# Motor_Driver.net
KiCad netlist of a schematic drawn in Altium Designer
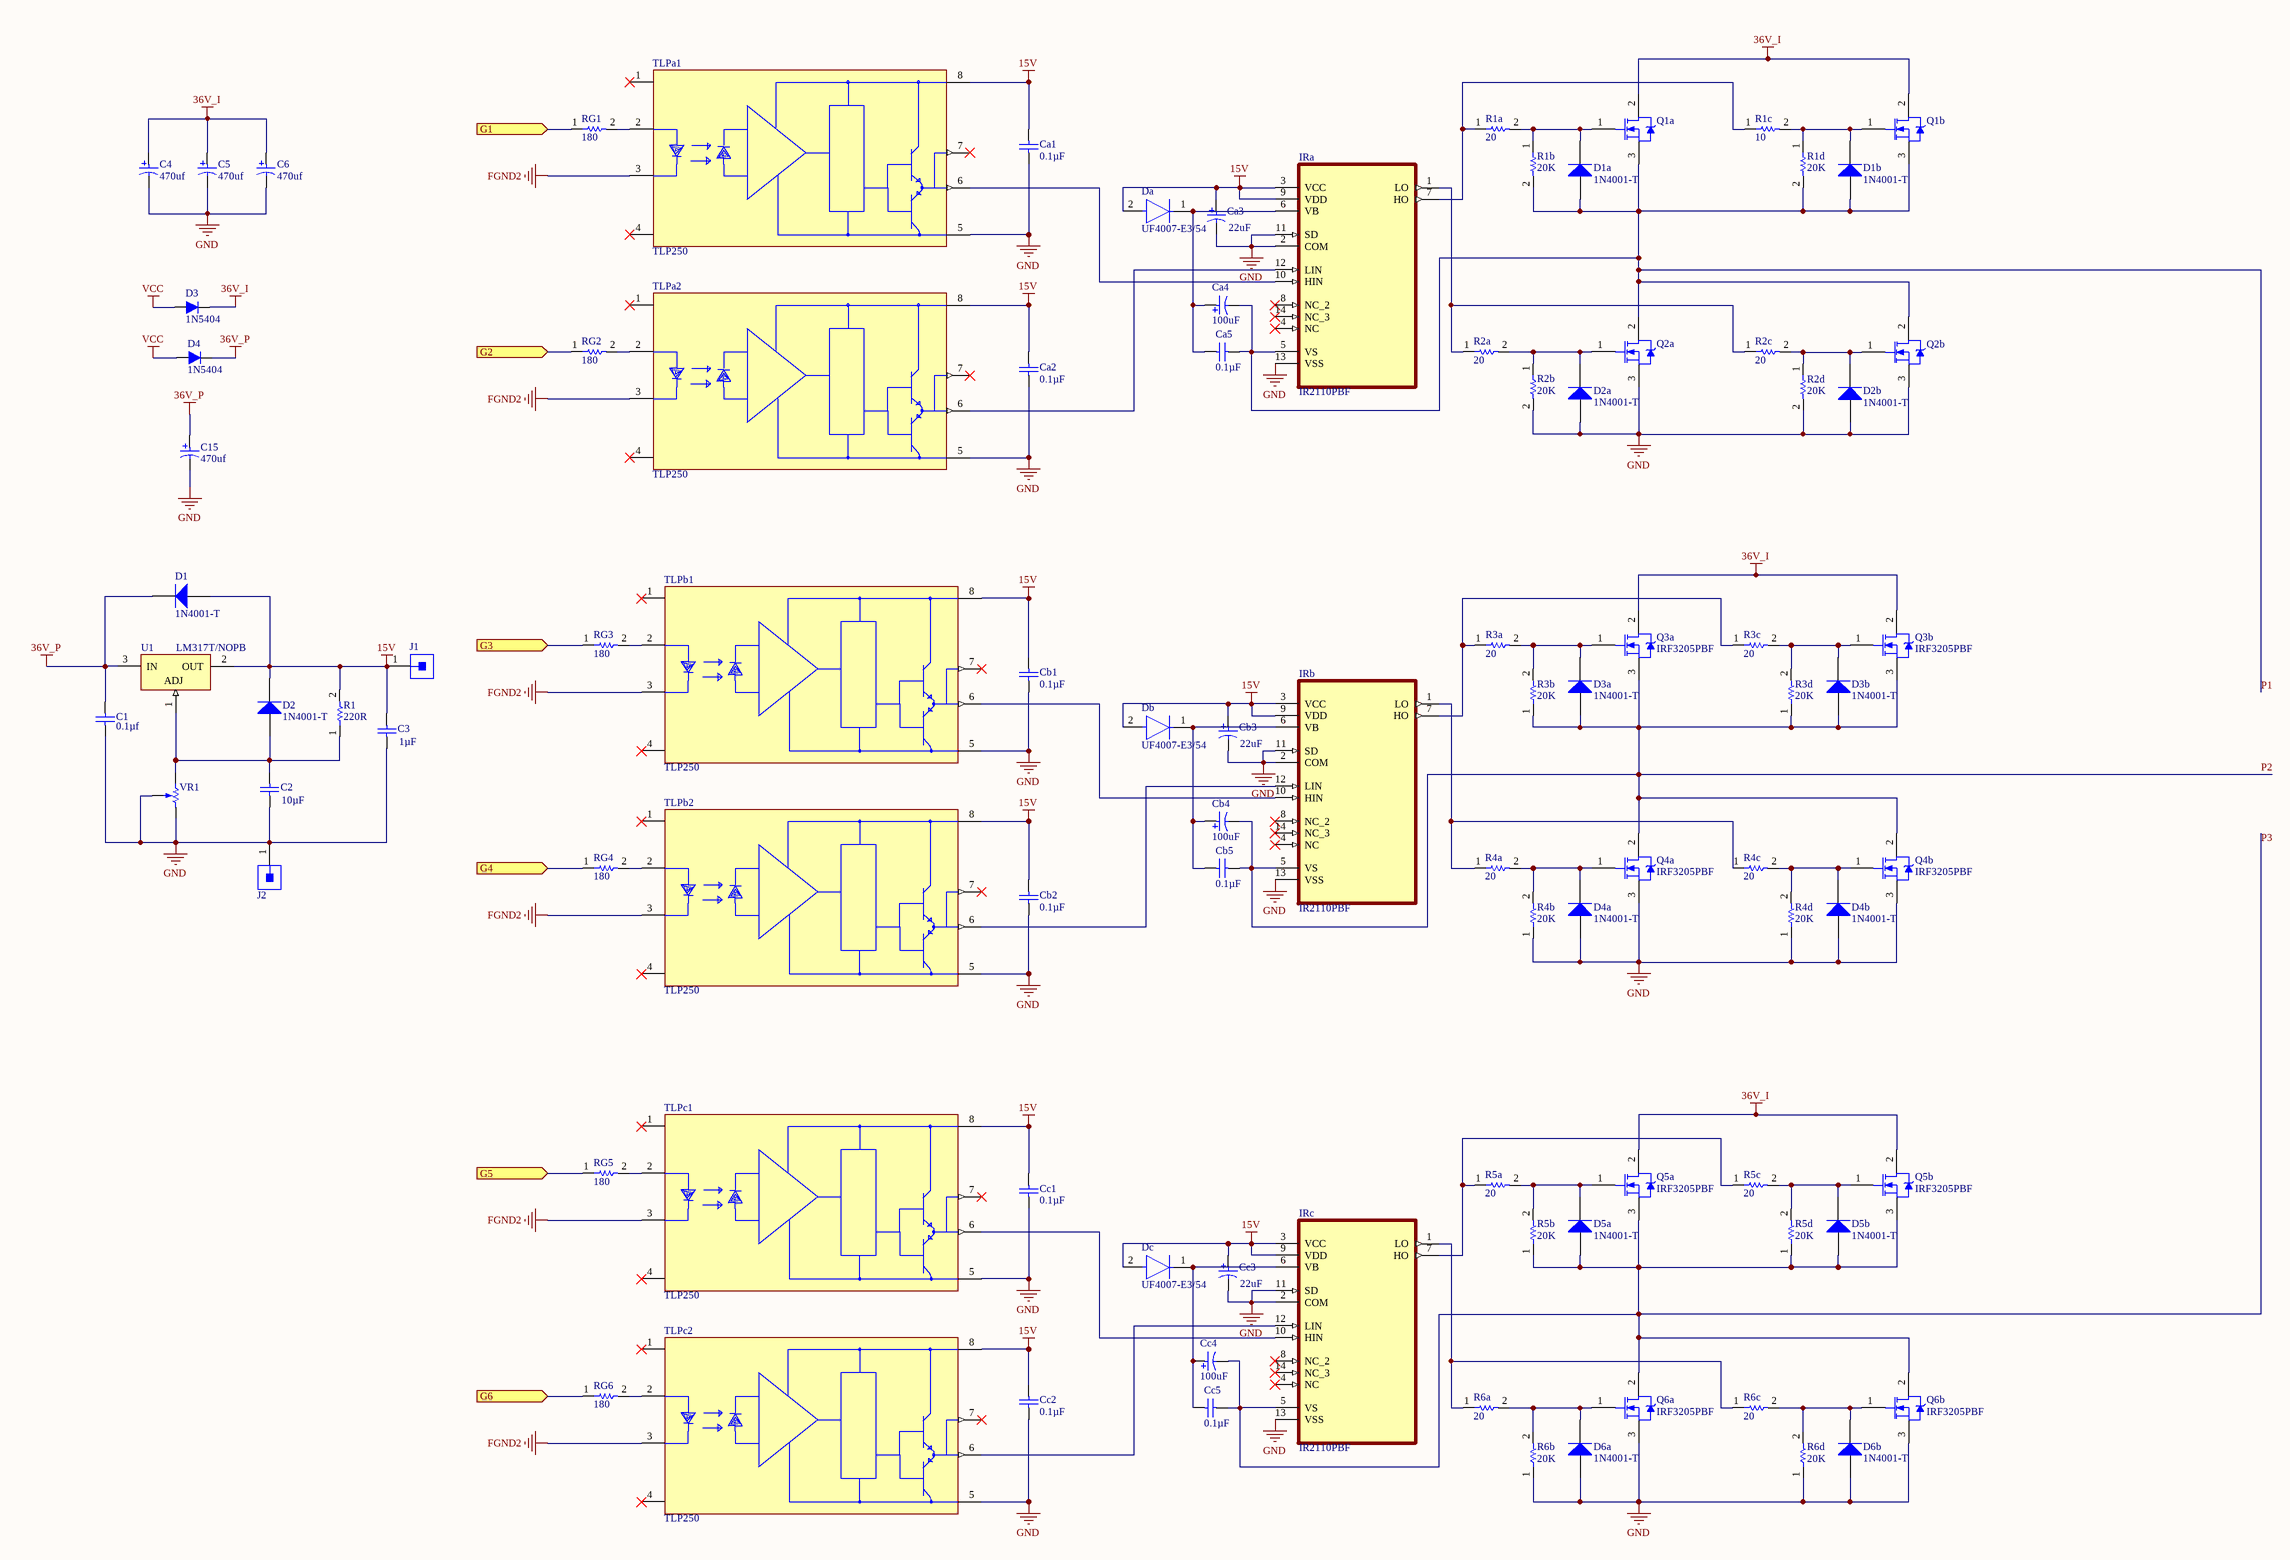
[diagram p0: Motor_Driver.SchDoc]

(export (version "E")
  (design (tool "Eeschema 10.0.6"))
  (components
    (comp (ref "C1")
      (value "0.1µf")
      (footprint "Cap-0.1uf-50V-Ceramic1")
      (description "Lead Capacitor X7R_EIA_ with Capacitance: 0.10F and Rated Voltage: 50Vdc")
      (fields (field (name "MP") "RDER71H104K0K1H03B") (field (name "MF") "Murata"))
      (libsource (lib "YAYAT-LIB") (part "Cap-0.1uf-50V-Ceramic_1"))
    )
    (comp (ref "C2")
      (value "K104K15X7RF5TL2")
      (footprint "Cap-0.1uf-50v-ceramic")
      (description "Ceramic Capacitor, 100 nF, +/- 10%, 50 V, -55 to 125 degC, 2-Pin THD, RoHS, Tape and Reel")
      (fields
        (field (name "MANUFACTURER") "Vishay")
        (field (name "TOLERANCE") "±10%")
        (field (name "CAPACITANCE") "10µF")
      )
      (libsource (lib "YAYAT-LIB") (part "Cap-0.1uf-50v-ceramic"))
    )
    (comp (ref "C3")
      (value "K104K15X7RF5TL2")
      (footprint "Cap-0.1uf-50v-ceramic")
      (description "Ceramic Capacitor, 100 nF, +/- 10%, 50 V, -55 to 125 degC, 2-Pin THD, RoHS, Tape and Reel")
      (fields
        (field (name "MANUFACTURER") "Vishay")
        (field (name "TOLERANCE") "±10%")
        (field (name "CAPACITANCE") "1µF")
      )
      (libsource (lib "YAYAT-LIB") (part "Cap-0.1uf-50v-ceramic"))
    )
    (comp (ref "C4")
      (value "470uf")
      (footprint "Cap-470uf-63v-radial")
      (description "Aluminum Electrolytic Capacitor, 470 uF, +/- 20%, 50 V, -40 to 85 degC, 2-Pin THD, RoHS, Bulk")
      (fields (field (name "TOLERANCE") "10%"))
      (libsource (lib "YAYAT-LIB") (part "Cap-470uf-63v-radial"))
    )
    (comp (ref "C5")
      (value "470uf")
      (footprint "Cap-470uf-63v-radial")
      (description "Aluminum Electrolytic Capacitor, 470 uF, +/- 20%, 50 V, -40 to 85 degC, 2-Pin THD, RoHS, Bulk")
      (fields (field (name "TOLERANCE") "10%"))
      (libsource (lib "YAYAT-LIB") (part "Cap-470uf-63v-radial"))
    )
    (comp (ref "C6")
      (value "470uf")
      (footprint "Cap-470uf-63v-radial")
      (description "Aluminum Electrolytic Capacitor, 470 uF, +/- 20%, 50 V, -40 to 85 degC, 2-Pin THD, RoHS, Bulk")
      (fields (field (name "TOLERANCE") "10%"))
      (libsource (lib "YAYAT-LIB") (part "Cap-470uf-63v-radial"))
    )
    (comp (ref "C15")
      (value "470uf")
      (footprint "Cap-470uf-63v-radial")
      (description "Aluminum Electrolytic Capacitor, 470 uF, +/- 20%, 50 V, -40 to 85 degC, 2-Pin THD, RoHS, Bulk")
      (fields (field (name "TOLERANCE") "10%"))
      (libsource (lib "YAYAT-LIB") (part "Cap-470uf-63v-radial"))
    )
    (comp (ref "Ca1")
      (value "0.1µF")
      (footprint "Cap-0.1uf-50V-Ceramic1")
      (description "Lead Capacitor X7R_EIA_ with Capacitance: 0.10F and Rated Voltage: 50Vdc")
      (fields (field (name "MP") "RDER71H104K0K1H03B") (field (name "MF") "Murata"))
      (libsource (lib "YAYAT-LIB") (part "Cap-0.1uf-50V-Ceramic_1"))
    )
    (comp (ref "Ca2")
      (value "0.1µF")
      (footprint "Cap-0.1uf-50V-Ceramic1")
      (description "Lead Capacitor X7R_EIA_ with Capacitance: 0.10F and Rated Voltage: 50Vdc")
      (fields (field (name "MP") "RDER71H104K0K1H03B") (field (name "MF") "Murata"))
      (libsource (lib "YAYAT-LIB") (part "Cap-0.1uf-50V-Ceramic_1"))
    )
    (comp (ref "Ca3")
      (value "ECA1HM220")
      (footprint "CAP-22uf-50v-radial")
      (description "Aluminum Electrolytic Capacitor, 22 uF, +/- 20%, 50 V, -40 to 85 degC, 2-Pin THD, RoHS, Bulk")
      (fields
        (field (name "VOLTAGE") "50V")
        (field (name "MANUFACTURER") "Panasonic")
        (field (name "CAPACITANCE") "22uF")
      )
      (libsource (lib "YAYAT-LIB") (part "Cap-22uf-50v-radial"))
    )
    (comp (ref "Ca4")
      (value "ECA1HM101")
      (footprint "Cap-100uf-50v-radial")
      (description "Aluminum Electrolytic Capacitor, 100 uF, +/- 20%, 50 V, -40 to 85 degC, 2-Pin THD, RoHS, Bulk")
      (fields
        (field (name "MANUFACTURER") "Panasonic")
        (field (name "VOLTAGE") "50V")
        (field (name "CAPACITANCE") "100uF")
      )
      (libsource (lib "YAYAT-LIB") (part "Cap-100uf-50v-radial"))
    )
    (comp (ref "Ca5")
      (value "0.1µF")
      (footprint "Cap-0.1uf-50V-Ceramic1")
      (description "Lead Capacitor X7R_EIA_ with Capacitance: 0.10F and Rated Voltage: 50Vdc")
      (fields (field (name "MP") "RDER71H104K0K1H03B") (field (name "MF") "Murata"))
      (libsource (lib "YAYAT-LIB") (part "Cap-0.1uf-50V-Ceramic_1"))
    )
    (comp (ref "Cb1")
      (value "0.1µF")
      (footprint "Cap-0.1uf-50V-Ceramic1")
      (description "Lead Capacitor X7R_EIA_ with Capacitance: 0.10F and Rated Voltage: 50Vdc")
      (fields (field (name "MP") "RDER71H104K0K1H03B") (field (name "MF") "Murata"))
      (libsource (lib "YAYAT-LIB") (part "Cap-0.1uf-50V-Ceramic_1"))
    )
    (comp (ref "Cb2")
      (value "0.1µF")
      (footprint "Cap-0.1uf-50V-Ceramic1")
      (description "Lead Capacitor X7R_EIA_ with Capacitance: 0.10F and Rated Voltage: 50Vdc")
      (fields (field (name "MP") "RDER71H104K0K1H03B") (field (name "MF") "Murata"))
      (libsource (lib "YAYAT-LIB") (part "Cap-0.1uf-50V-Ceramic_1"))
    )
    (comp (ref "Cb3")
      (value "ECA1HM220")
      (footprint "CAP-22uf-50v-radial")
      (description "Aluminum Electrolytic Capacitor, 22 uF, +/- 20%, 50 V, -40 to 85 degC, 2-Pin THD, RoHS, Bulk")
      (fields
        (field (name "VOLTAGE") "50V")
        (field (name "MANUFACTURER") "Panasonic")
        (field (name "CAPACITANCE") "22uF")
      )
      (libsource (lib "YAYAT-LIB") (part "Cap-22uf-50v-radial"))
    )
    (comp (ref "Cb4")
      (value "ECA1HM101")
      (footprint "Cap-100uf-50v-radial")
      (description "Aluminum Electrolytic Capacitor, 100 uF, +/- 20%, 50 V, -40 to 85 degC, 2-Pin THD, RoHS, Bulk")
      (fields
        (field (name "MANUFACTURER") "Panasonic")
        (field (name "VOLTAGE") "50V")
        (field (name "CAPACITANCE") "100uF")
      )
      (libsource (lib "YAYAT-LIB") (part "Cap-100uf-50v-radial"))
    )
    (comp (ref "Cb5")
      (value "0.1µF")
      (footprint "Cap-0.1uf-50V-Ceramic1")
      (description "Lead Capacitor X7R_EIA_ with Capacitance: 0.10F and Rated Voltage: 50Vdc")
      (fields (field (name "MP") "RDER71H104K0K1H03B") (field (name "MF") "Murata"))
      (libsource (lib "YAYAT-LIB") (part "Cap-0.1uf-50V-Ceramic_1"))
    )
    (comp (ref "Cc1")
      (value "0.1µF")
      (footprint "Cap-0.1uf-50V-Ceramic1")
      (description "Lead Capacitor X7R_EIA_ with Capacitance: 0.10F and Rated Voltage: 50Vdc")
      (fields (field (name "MP") "RDER71H104K0K1H03B") (field (name "MF") "Murata"))
      (libsource (lib "YAYAT-LIB") (part "Cap-0.1uf-50V-Ceramic_1"))
    )
    (comp (ref "Cc2")
      (value "0.1µF")
      (footprint "Cap-0.1uf-50V-Ceramic1")
      (description "Lead Capacitor X7R_EIA_ with Capacitance: 0.10F and Rated Voltage: 50Vdc")
      (fields (field (name "MP") "RDER71H104K0K1H03B") (field (name "MF") "Murata"))
      (libsource (lib "YAYAT-LIB") (part "Cap-0.1uf-50V-Ceramic_1"))
    )
    (comp (ref "Cc3")
      (value "ECA1HM220")
      (footprint "CAP-22uf-50v-radial")
      (description "Aluminum Electrolytic Capacitor, 22 uF, +/- 20%, 50 V, -40 to 85 degC, 2-Pin THD, RoHS, Bulk")
      (fields
        (field (name "VOLTAGE") "50V")
        (field (name "MANUFACTURER") "Panasonic")
        (field (name "CAPACITANCE") "22uF")
      )
      (libsource (lib "YAYAT-LIB") (part "Cap-22uf-50v-radial"))
    )
    (comp (ref "Cc4")
      (value "ECA1HM101")
      (footprint "Cap-100uf-50v-radial")
      (description "Aluminum Electrolytic Capacitor, 100 uF, +/- 20%, 50 V, -40 to 85 degC, 2-Pin THD, RoHS, Bulk")
      (fields
        (field (name "MANUFACTURER") "Panasonic")
        (field (name "VOLTAGE") "50V")
        (field (name "CAPACITANCE") "100uF")
      )
      (libsource (lib "YAYAT-LIB") (part "Cap-100uf-50v-radial"))
    )
    (comp (ref "Cc5")
      (value "0.1µF")
      (footprint "Cap-0.1uf-50V-Ceramic1")
      (description "Lead Capacitor X7R_EIA_ with Capacitance: 0.10F and Rated Voltage: 50Vdc")
      (fields (field (name "MP") "RDER71H104K0K1H03B") (field (name "MF") "Murata"))
      (libsource (lib "YAYAT-LIB") (part "Cap-0.1uf-50V-Ceramic_1"))
    )
    (comp (ref "D1")
      (value "1N4001-T")
      (footprint "Diode-1N4001")
      (description "1.0 A Rectifier, 15 pF, 50 V, -65 to 150 degC, 2-Pin DO-41 Plastic, RoHS, Tape and Reel")
      (fields (field (name "MANUFACTURER") "Diodes Inc"))
      (libsource (lib "YAYAT-LIB") (part "Diode-1N4001"))
    )
    (comp (ref "D1a")
      (value "1N4001-T")
      (footprint "Diode-1N4001")
      (description "1.0 A Rectifier, 15 pF, 50 V, -65 to 150 degC, 2-Pin DO-41 Plastic, RoHS, Tape and Reel")
      (fields (field (name "MANUFACTURER") "Diodes Inc"))
      (libsource (lib "YAYAT-LIB") (part "Diode-1N4001"))
    )
    (comp (ref "D1b")
      (value "1N4001-T")
      (footprint "Diode-1N4001")
      (description "1.0 A Rectifier, 15 pF, 50 V, -65 to 150 degC, 2-Pin DO-41 Plastic, RoHS, Tape and Reel")
      (fields (field (name "MANUFACTURER") "Diodes Inc"))
      (libsource (lib "YAYAT-LIB") (part "Diode-1N4001"))
    )
    (comp (ref "D2")
      (value "1N4001-T")
      (footprint "Diode-1N4001")
      (description "1.0 A Rectifier, 15 pF, 50 V, -65 to 150 degC, 2-Pin DO-41 Plastic, RoHS, Tape and Reel")
      (fields (field (name "MANUFACTURER") "Diodes Inc"))
      (libsource (lib "YAYAT-LIB") (part "Diode-1N4001"))
    )
    (comp (ref "D2a")
      (value "1N4001-T")
      (footprint "Diode-1N4001")
      (description "1.0 A Rectifier, 15 pF, 50 V, -65 to 150 degC, 2-Pin DO-41 Plastic, RoHS, Tape and Reel")
      (fields (field (name "MANUFACTURER") "Diodes Inc"))
      (libsource (lib "YAYAT-LIB") (part "Diode-1N4001"))
    )
    (comp (ref "D2b")
      (value "1N4001-T")
      (footprint "Diode-1N4001")
      (description "1.0 A Rectifier, 15 pF, 50 V, -65 to 150 degC, 2-Pin DO-41 Plastic, RoHS, Tape and Reel")
      (fields (field (name "MANUFACTURER") "Diodes Inc"))
      (libsource (lib "YAYAT-LIB") (part "Diode-1N4001"))
    )
    (comp (ref "D3")
      (value "1N5404")
      (footprint "Diode-1N5404")
      (description "Standard Recovery Rectifier, 2-Pin Axial_Lead, Pb-Free, Bulk Box")
      (fields (field (name "MANUFACTURER") "On Semiconductor"))
      (libsource (lib "YAYAT-LIB") (part "Diode-1N5404"))
    )
    (comp (ref "D3a")
      (value "1N4001-T")
      (footprint "Diode-1N4001")
      (description "1.0 A Rectifier, 15 pF, 50 V, -65 to 150 degC, 2-Pin DO-41 Plastic, RoHS, Tape and Reel")
      (fields (field (name "MANUFACTURER") "Diodes Inc"))
      (libsource (lib "YAYAT-LIB") (part "Diode-1N4001"))
    )
    (comp (ref "D3b")
      (value "1N4001-T")
      (footprint "Diode-1N4001")
      (description "1.0 A Rectifier, 15 pF, 50 V, -65 to 150 degC, 2-Pin DO-41 Plastic, RoHS, Tape and Reel")
      (fields (field (name "MANUFACTURER") "Diodes Inc"))
      (libsource (lib "YAYAT-LIB") (part "Diode-1N4001"))
    )
    (comp (ref "D4")
      (value "1N5404")
      (footprint "Diode-1N5404")
      (description "Standard Recovery Rectifier, 2-Pin Axial_Lead, Pb-Free, Bulk Box")
      (fields (field (name "MANUFACTURER") "On Semiconductor"))
      (libsource (lib "YAYAT-LIB") (part "Diode-1N5404"))
    )
    (comp (ref "D4a")
      (value "1N4001-T")
      (footprint "Diode-1N4001")
      (description "1.0 A Rectifier, 15 pF, 50 V, -65 to 150 degC, 2-Pin DO-41 Plastic, RoHS, Tape and Reel")
      (fields (field (name "MANUFACTURER") "Diodes Inc"))
      (libsource (lib "YAYAT-LIB") (part "Diode-1N4001"))
    )
    (comp (ref "D4b")
      (value "1N4001-T")
      (footprint "Diode-1N4001")
      (description "1.0 A Rectifier, 15 pF, 50 V, -65 to 150 degC, 2-Pin DO-41 Plastic, RoHS, Tape and Reel")
      (fields (field (name "MANUFACTURER") "Diodes Inc"))
      (libsource (lib "YAYAT-LIB") (part "Diode-1N4001"))
    )
    (comp (ref "D5a")
      (value "1N4001-T")
      (footprint "Diode-1N4001")
      (description "1.0 A Rectifier, 15 pF, 50 V, -65 to 150 degC, 2-Pin DO-41 Plastic, RoHS, Tape and Reel")
      (fields (field (name "MANUFACTURER") "Diodes Inc"))
      (libsource (lib "YAYAT-LIB") (part "Diode-1N4001"))
    )
    (comp (ref "D5b")
      (value "1N4001-T")
      (footprint "Diode-1N4001")
      (description "1.0 A Rectifier, 15 pF, 50 V, -65 to 150 degC, 2-Pin DO-41 Plastic, RoHS, Tape and Reel")
      (fields (field (name "MANUFACTURER") "Diodes Inc"))
      (libsource (lib "YAYAT-LIB") (part "Diode-1N4001"))
    )
    (comp (ref "D6a")
      (value "1N4001-T")
      (footprint "Diode-1N4001")
      (description "1.0 A Rectifier, 15 pF, 50 V, -65 to 150 degC, 2-Pin DO-41 Plastic, RoHS, Tape and Reel")
      (fields (field (name "MANUFACTURER") "Diodes Inc"))
      (libsource (lib "YAYAT-LIB") (part "Diode-1N4001"))
    )
    (comp (ref "D6b")
      (value "1N4001-T")
      (footprint "Diode-1N4001")
      (description "1.0 A Rectifier, 15 pF, 50 V, -65 to 150 degC, 2-Pin DO-41 Plastic, RoHS, Tape and Reel")
      (fields (field (name "MANUFACTURER") "Diodes Inc"))
      (libsource (lib "YAYAT-LIB") (part "Diode-1N4001"))
    )
    (comp (ref "Da")
      (value "UF4007-E3/54")
      (footprint "Diode-UF4007")
      (description "DIODE GEN PURP 1KV 1A DO204AL")
      (fields
        (field (name "MANUFACTURER") "Vishay")
        (field (name "OCTOPART") "https://octopart.com/uf4007-e3%2F54-vishay-42333894")
      )
      (libsource (lib "YAYAT-LIB") (part "Diode-UF4007"))
    )
    (comp (ref "Db")
      (value "UF4007-E3/54")
      (footprint "Diode-UF4007")
      (description "DIODE GEN PURP 1KV 1A DO204AL")
      (fields
        (field (name "MANUFACTURER") "Vishay")
        (field (name "OCTOPART") "https://octopart.com/uf4007-e3%2F54-vishay-42333894")
      )
      (libsource (lib "YAYAT-LIB") (part "Diode-UF4007"))
    )
    (comp (ref "Dc")
      (value "UF4007-E3/54")
      (footprint "Diode-UF4007")
      (description "DIODE GEN PURP 1KV 1A DO204AL")
      (fields
        (field (name "MANUFACTURER") "Vishay")
        (field (name "OCTOPART") "https://octopart.com/uf4007-e3%2F54-vishay-42333894")
      )
      (libsource (lib "YAYAT-LIB") (part "Diode-UF4007"))
    )
    (comp (ref "IRa")
      (value "IR2110PBF")
      (footprint "Mosfet-Driver-IR2110PBF")
      (fields (field (name "MF") "Infineon"))
      (libsource (lib "YAYAT-LIB") (part "IR2110PBF"))
    )
    (comp (ref "IRb")
      (value "IR2110PBF")
      (footprint "Mosfet-Driver-IR2110PBF")
      (fields (field (name "MF") "Infineon"))
      (libsource (lib "YAYAT-LIB") (part "IR2110PBF"))
    )
    (comp (ref "IRc")
      (value "IR2110PBF")
      (footprint "Mosfet-Driver-IR2110PBF")
      (fields (field (name "MF") "Infineon"))
      (libsource (lib "YAYAT-LIB") (part "IR2110PBF"))
    )
    (comp (ref "J1")
      (value "61300111121")
      (footprint "PIN-HEADER-1PIN")
      (description "THT Vertical Pin Header WR-PHD, Pitch 2.54 mm, Single Row, 1 pins")
      (fields (field (name "MANUFACTURER") "Wurth Elektronik") (field (name "PUBLISHER") "WurthElektronik"))
      (libsource (lib "YAYAT-LIB") (part "Pin-Header-1Pin"))
    )
    (comp (ref "J2")
      (value "61300111121")
      (footprint "PIN-HEADER-1PIN")
      (description "THT Vertical Pin Header WR-PHD, Pitch 2.54 mm, Single Row, 1 pins")
      (fields (field (name "MANUFACTURER") "Wurth Elektronik") (field (name "PUBLISHER") "WurthElektronik"))
      (libsource (lib "") (part "Pin-Header-1Pin_1"))
    )
    (comp (ref "Q1a")
      (value "IRF3205PBF")
      (footprint "Mosfet-IRF3205")
      (description "HEXFET(R) Power N-Channel MOSFET, 55 V, 110 A, -55 to 117 degC, 3-Pin TO-220AB, RoHS, Rail/Tube")
      (fields (field (name "MANUFACTURER") "International Rectifier"))
      (libsource (lib "YAYAT-LIB") (part "Mosfet-IRF3205"))
    )
    (comp (ref "Q1b")
      (value "IRF3205PBF")
      (footprint "Mosfet-IRF3205")
      (description "HEXFET(R) Power N-Channel MOSFET, 55 V, 110 A, -55 to 117 degC, 3-Pin TO-220AB, RoHS, Rail/Tube")
      (fields (field (name "MANUFACTURER") "International Rectifier"))
      (libsource (lib "YAYAT-LIB") (part "Mosfet-IRF3205"))
    )
    (comp (ref "Q2a")
      (value "IRF3205PBF")
      (footprint "Mosfet-IRF3205")
      (description "HEXFET(R) Power N-Channel MOSFET, 55 V, 110 A, -55 to 117 degC, 3-Pin TO-220AB, RoHS, Rail/Tube")
      (fields (field (name "MANUFACTURER") "International Rectifier"))
      (libsource (lib "YAYAT-LIB") (part "Mosfet-IRF3205"))
    )
    (comp (ref "Q2b")
      (value "IRF3205PBF")
      (footprint "Mosfet-IRF3205")
      (description "HEXFET(R) Power N-Channel MOSFET, 55 V, 110 A, -55 to 117 degC, 3-Pin TO-220AB, RoHS, Rail/Tube")
      (fields (field (name "MANUFACTURER") "International Rectifier"))
      (libsource (lib "YAYAT-LIB") (part "Mosfet-IRF3205"))
    )
    (comp (ref "Q3a")
      (value "IRF3205PBF")
      (footprint "Mosfet-IRF3205")
      (description "HEXFET(R) Power N-Channel MOSFET, 55 V, 110 A, -55 to 117 degC, 3-Pin TO-220AB, RoHS, Rail/Tube")
      (fields (field (name "MANUFACTURER") "International Rectifier"))
      (libsource (lib "YAYAT-LIB") (part "Mosfet-IRF3205"))
    )
    (comp (ref "Q3b")
      (value "IRF3205PBF")
      (footprint "Mosfet-IRF3205")
      (description "HEXFET(R) Power N-Channel MOSFET, 55 V, 110 A, -55 to 117 degC, 3-Pin TO-220AB, RoHS, Rail/Tube")
      (fields (field (name "MANUFACTURER") "International Rectifier"))
      (libsource (lib "YAYAT-LIB") (part "Mosfet-IRF3205"))
    )
    (comp (ref "Q4a")
      (value "IRF3205PBF")
      (footprint "Mosfet-IRF3205")
      (description "HEXFET(R) Power N-Channel MOSFET, 55 V, 110 A, -55 to 117 degC, 3-Pin TO-220AB, RoHS, Rail/Tube")
      (fields (field (name "MANUFACTURER") "International Rectifier"))
      (libsource (lib "YAYAT-LIB") (part "Mosfet-IRF3205"))
    )
    (comp (ref "Q4b")
      (value "IRF3205PBF")
      (footprint "Mosfet-IRF3205")
      (description "HEXFET(R) Power N-Channel MOSFET, 55 V, 110 A, -55 to 117 degC, 3-Pin TO-220AB, RoHS, Rail/Tube")
      (fields (field (name "MANUFACTURER") "International Rectifier"))
      (libsource (lib "YAYAT-LIB") (part "Mosfet-IRF3205"))
    )
    (comp (ref "Q5a")
      (value "IRF3205PBF")
      (footprint "Mosfet-IRF3205")
      (description "HEXFET(R) Power N-Channel MOSFET, 55 V, 110 A, -55 to 117 degC, 3-Pin TO-220AB, RoHS, Rail/Tube")
      (fields (field (name "MANUFACTURER") "International Rectifier"))
      (libsource (lib "YAYAT-LIB") (part "Mosfet-IRF3205"))
    )
    (comp (ref "Q5b")
      (value "IRF3205PBF")
      (footprint "Mosfet-IRF3205")
      (description "HEXFET(R) Power N-Channel MOSFET, 55 V, 110 A, -55 to 117 degC, 3-Pin TO-220AB, RoHS, Rail/Tube")
      (fields (field (name "MANUFACTURER") "International Rectifier"))
      (libsource (lib "YAYAT-LIB") (part "Mosfet-IRF3205"))
    )
    (comp (ref "Q6a")
      (value "IRF3205PBF")
      (footprint "Mosfet-IRF3205")
      (description "HEXFET(R) Power N-Channel MOSFET, 55 V, 110 A, -55 to 117 degC, 3-Pin TO-220AB, RoHS, Rail/Tube")
      (fields (field (name "MANUFACTURER") "International Rectifier"))
      (libsource (lib "YAYAT-LIB") (part "Mosfet-IRF3205"))
    )
    (comp (ref "Q6b")
      (value "IRF3205PBF")
      (footprint "Mosfet-IRF3205")
      (description "HEXFET(R) Power N-Channel MOSFET, 55 V, 110 A, -55 to 117 degC, 3-Pin TO-220AB, RoHS, Rail/Tube")
      (fields (field (name "MANUFACTURER") "International Rectifier"))
      (libsource (lib "YAYAT-LIB") (part "Mosfet-IRF3205"))
    )
    (comp (ref "R1")
      (value "220R")
      (footprint "Resistor-1-Watt")
      (description "Resistor")
      (fields
        (field (name "MANUFACTURER_PART_NUMBER") "OK1025E-R52")
        (field (name "MOUSER PART NUMBER") "588-OK1025E-R52")
      )
      (libsource (lib "YAYAT-LIB") (part "Resistor-1-Watt"))
    )
    (comp (ref "R1a")
      (value "20")
      (footprint "Resistor-1-Watt")
      (description "Resistor")
      (fields
        (field (name "MANUFACTURER_PART_NUMBER") "OK1025E-R52")
        (field (name "MOUSER PART NUMBER") "588-OK1025E-R52")
      )
      (libsource (lib "YAYAT-LIB") (part "Resistor-1-Watt"))
    )
    (comp (ref "R1b")
      (value "20K")
      (footprint "Resistor-1-Watt")
      (description "Resistor")
      (fields
        (field (name "MANUFACTURER_PART_NUMBER") "OK1025E-R52")
        (field (name "MOUSER PART NUMBER") "588-OK1025E-R52")
      )
      (libsource (lib "YAYAT-LIB") (part "Resistor-1-Watt"))
    )
    (comp (ref "R1c")
      (value "10")
      (footprint "Resistor-1-Watt")
      (description "Resistor")
      (fields
        (field (name "MANUFACTURER_PART_NUMBER") "OK1025E-R52")
        (field (name "MOUSER PART NUMBER") "588-OK1025E-R52")
      )
      (libsource (lib "YAYAT-LIB") (part "Resistor-1-Watt"))
    )
    (comp (ref "R1d")
      (value "20K")
      (footprint "Resistor-1-Watt")
      (description "Resistor")
      (fields
        (field (name "MANUFACTURER_PART_NUMBER") "OK1025E-R52")
        (field (name "MOUSER PART NUMBER") "588-OK1025E-R52")
      )
      (libsource (lib "YAYAT-LIB") (part "Resistor-1-Watt"))
    )
    (comp (ref "R2a")
      (value "20")
      (footprint "Resistor-1-Watt")
      (description "Resistor")
      (fields
        (field (name "MANUFACTURER_PART_NUMBER") "OK1025E-R52")
        (field (name "MOUSER PART NUMBER") "588-OK1025E-R52")
      )
      (libsource (lib "YAYAT-LIB") (part "Resistor-1-Watt"))
    )
    (comp (ref "R2b")
      (value "20K")
      (footprint "Resistor-1-Watt")
      (description "Resistor")
      (fields
        (field (name "MANUFACTURER_PART_NUMBER") "OK1025E-R52")
        (field (name "MOUSER PART NUMBER") "588-OK1025E-R52")
      )
      (libsource (lib "YAYAT-LIB") (part "Resistor-1-Watt"))
    )
    (comp (ref "R2c")
      (value "20")
      (footprint "Resistor-1-Watt")
      (description "Resistor")
      (fields
        (field (name "MANUFACTURER_PART_NUMBER") "OK1025E-R52")
        (field (name "MOUSER PART NUMBER") "588-OK1025E-R52")
      )
      (libsource (lib "YAYAT-LIB") (part "Resistor-1-Watt"))
    )
    (comp (ref "R2d")
      (value "20K")
      (footprint "Resistor-1-Watt")
      (description "Resistor")
      (fields
        (field (name "MANUFACTURER_PART_NUMBER") "OK1025E-R52")
        (field (name "MOUSER PART NUMBER") "588-OK1025E-R52")
      )
      (libsource (lib "YAYAT-LIB") (part "Resistor-1-Watt"))
    )
    (comp (ref "R3a")
      (value "20")
      (footprint "Resistor-1-Watt")
      (description "Resistor")
      (fields
        (field (name "MANUFACTURER_PART_NUMBER") "OK1025E-R52")
        (field (name "MOUSER PART NUMBER") "588-OK1025E-R52")
      )
      (libsource (lib "YAYAT-LIB") (part "Resistor-1-Watt"))
    )
    (comp (ref "R3b")
      (value "20K")
      (footprint "Resistor-1-Watt")
      (description "Resistor")
      (fields
        (field (name "MANUFACTURER_PART_NUMBER") "OK1025E-R52")
        (field (name "MOUSER PART NUMBER") "588-OK1025E-R52")
      )
      (libsource (lib "YAYAT-LIB") (part "Resistor-1-Watt"))
    )
    (comp (ref "R3c")
      (value "20")
      (footprint "Resistor-1-Watt")
      (description "Resistor")
      (fields
        (field (name "MANUFACTURER_PART_NUMBER") "OK1025E-R52")
        (field (name "MOUSER PART NUMBER") "588-OK1025E-R52")
      )
      (libsource (lib "YAYAT-LIB") (part "Resistor-1-Watt"))
    )
    (comp (ref "R3d")
      (value "20K")
      (footprint "Resistor-1-Watt")
      (description "Resistor")
      (fields
        (field (name "MANUFACTURER_PART_NUMBER") "OK1025E-R52")
        (field (name "MOUSER PART NUMBER") "588-OK1025E-R52")
      )
      (libsource (lib "YAYAT-LIB") (part "Resistor-1-Watt"))
    )
    (comp (ref "R4a")
      (value "20")
      (footprint "Resistor-1-Watt")
      (description "Resistor")
      (fields
        (field (name "MANUFACTURER_PART_NUMBER") "OK1025E-R52")
        (field (name "MOUSER PART NUMBER") "588-OK1025E-R52")
      )
      (libsource (lib "YAYAT-LIB") (part "Resistor-1-Watt"))
    )
    (comp (ref "R4b")
      (value "20K")
      (footprint "Resistor-1-Watt")
      (description "Resistor")
      (fields
        (field (name "MANUFACTURER_PART_NUMBER") "OK1025E-R52")
        (field (name "MOUSER PART NUMBER") "588-OK1025E-R52")
      )
      (libsource (lib "YAYAT-LIB") (part "Resistor-1-Watt"))
    )
    (comp (ref "R4c")
      (value "20")
      (footprint "Resistor-1-Watt")
      (description "Resistor")
      (fields
        (field (name "MANUFACTURER_PART_NUMBER") "OK1025E-R52")
        (field (name "MOUSER PART NUMBER") "588-OK1025E-R52")
      )
      (libsource (lib "YAYAT-LIB") (part "Resistor-1-Watt"))
    )
    (comp (ref "R4d")
      (value "20K")
      (footprint "Resistor-1-Watt")
      (description "Resistor")
      (fields
        (field (name "MANUFACTURER_PART_NUMBER") "OK1025E-R52")
        (field (name "MOUSER PART NUMBER") "588-OK1025E-R52")
      )
      (libsource (lib "YAYAT-LIB") (part "Resistor-1-Watt"))
    )
    (comp (ref "R5a")
      (value "20")
      (footprint "Resistor-1-Watt")
      (description "Resistor")
      (fields
        (field (name "MANUFACTURER_PART_NUMBER") "OK1025E-R52")
        (field (name "MOUSER PART NUMBER") "588-OK1025E-R52")
      )
      (libsource (lib "YAYAT-LIB") (part "Resistor-1-Watt"))
    )
    (comp (ref "R5b")
      (value "20K")
      (footprint "Resistor-1-Watt")
      (description "Resistor")
      (fields
        (field (name "MANUFACTURER_PART_NUMBER") "OK1025E-R52")
        (field (name "MOUSER PART NUMBER") "588-OK1025E-R52")
      )
      (libsource (lib "YAYAT-LIB") (part "Resistor-1-Watt"))
    )
    (comp (ref "R5c")
      (value "20")
      (footprint "Resistor-1-Watt")
      (description "Resistor")
      (fields
        (field (name "MANUFACTURER_PART_NUMBER") "OK1025E-R52")
        (field (name "MOUSER PART NUMBER") "588-OK1025E-R52")
      )
      (libsource (lib "YAYAT-LIB") (part "Resistor-1-Watt"))
    )
    (comp (ref "R5d")
      (value "20K")
      (footprint "Resistor-1-Watt")
      (description "Resistor")
      (fields
        (field (name "MANUFACTURER_PART_NUMBER") "OK1025E-R52")
        (field (name "MOUSER PART NUMBER") "588-OK1025E-R52")
      )
      (libsource (lib "YAYAT-LIB") (part "Resistor-1-Watt"))
    )
    (comp (ref "R6a")
      (value "20")
      (footprint "Resistor-1-Watt")
      (description "Resistor")
      (fields
        (field (name "MANUFACTURER_PART_NUMBER") "OK1025E-R52")
        (field (name "MOUSER PART NUMBER") "588-OK1025E-R52")
      )
      (libsource (lib "YAYAT-LIB") (part "Resistor-1-Watt"))
    )
    (comp (ref "R6b")
      (value "20K")
      (footprint "Resistor-1-Watt")
      (description "Resistor")
      (fields
        (field (name "MANUFACTURER_PART_NUMBER") "OK1025E-R52")
        (field (name "MOUSER PART NUMBER") "588-OK1025E-R52")
      )
      (libsource (lib "YAYAT-LIB") (part "Resistor-1-Watt"))
    )
    (comp (ref "R6c")
      (value "20")
      (footprint "Resistor-1-Watt")
      (description "Resistor")
      (fields
        (field (name "MANUFACTURER_PART_NUMBER") "OK1025E-R52")
        (field (name "MOUSER PART NUMBER") "588-OK1025E-R52")
      )
      (libsource (lib "YAYAT-LIB") (part "Resistor-1-Watt"))
    )
    (comp (ref "R6d")
      (value "20K")
      (footprint "Resistor-1-Watt")
      (description "Resistor")
      (fields
        (field (name "MANUFACTURER_PART_NUMBER") "OK1025E-R52")
        (field (name "MOUSER PART NUMBER") "588-OK1025E-R52")
      )
      (libsource (lib "YAYAT-LIB") (part "Resistor-1-Watt"))
    )
    (comp (ref "RG1")
      (value "180")
      (footprint "Resistor-1-Watt")
      (description "Resistor")
      (fields
        (field (name "MANUFACTURER_PART_NUMBER") "OK1025E-R52")
        (field (name "MOUSER PART NUMBER") "588-OK1025E-R52")
      )
      (libsource (lib "YAYAT-LIB") (part "Resistor-1-Watt"))
    )
    (comp (ref "RG2")
      (value "180")
      (footprint "Resistor-1-Watt")
      (description "Resistor")
      (fields
        (field (name "MANUFACTURER_PART_NUMBER") "OK1025E-R52")
        (field (name "MOUSER PART NUMBER") "588-OK1025E-R52")
      )
      (libsource (lib "YAYAT-LIB") (part "Resistor-1-Watt"))
    )
    (comp (ref "RG3")
      (value "180")
      (footprint "Resistor-1-Watt")
      (description "Resistor")
      (fields
        (field (name "MANUFACTURER_PART_NUMBER") "OK1025E-R52")
        (field (name "MOUSER PART NUMBER") "588-OK1025E-R52")
      )
      (libsource (lib "YAYAT-LIB") (part "Resistor-1-Watt"))
    )
    (comp (ref "RG4")
      (value "180")
      (footprint "Resistor-1-Watt")
      (description "Resistor")
      (fields
        (field (name "MANUFACTURER_PART_NUMBER") "OK1025E-R52")
        (field (name "MOUSER PART NUMBER") "588-OK1025E-R52")
      )
      (libsource (lib "YAYAT-LIB") (part "Resistor-1-Watt"))
    )
    (comp (ref "RG5")
      (value "180")
      (footprint "Resistor-1-Watt")
      (description "Resistor")
      (fields
        (field (name "MANUFACTURER_PART_NUMBER") "OK1025E-R52")
        (field (name "MOUSER PART NUMBER") "588-OK1025E-R52")
      )
      (libsource (lib "YAYAT-LIB") (part "Resistor-1-Watt"))
    )
    (comp (ref "RG6")
      (value "180")
      (footprint "Resistor-1-Watt")
      (description "Resistor")
      (fields
        (field (name "MANUFACTURER_PART_NUMBER") "OK1025E-R52")
        (field (name "MOUSER PART NUMBER") "588-OK1025E-R52")
      )
      (libsource (lib "YAYAT-LIB") (part "Resistor-1-Watt"))
    )
    (comp (ref "TLPa1")
      (value "TLP250")
      (footprint "Opto-Coupler-TLP250")
      (description "Optocoupler Drive Push-Pull 1-CH 30V 600V 8-Pin PDIP")
      (fields
        (field (name "MANUFACTURER") "TOSHIBA")
        (field (name "OCTOPART") "https://octopart.com/tlp-250-toshiba-99104964")
      )
      (libsource (lib "YAYAT-LIB") (part "TLP250"))
    )
    (comp (ref "TLPa2")
      (value "TLP250")
      (footprint "Opto-Coupler-TLP250")
      (description "Optocoupler Drive Push-Pull 1-CH 30V 600V 8-Pin PDIP")
      (fields
        (field (name "MANUFACTURER") "TOSHIBA")
        (field (name "OCTOPART") "https://octopart.com/tlp-250-toshiba-99104964")
      )
      (libsource (lib "YAYAT-LIB") (part "TLP250"))
    )
    (comp (ref "TLPb1")
      (value "TLP250")
      (footprint "Opto-Coupler-TLP250")
      (description "Optocoupler Drive Push-Pull 1-CH 30V 600V 8-Pin PDIP")
      (fields
        (field (name "MANUFACTURER") "TOSHIBA")
        (field (name "OCTOPART") "https://octopart.com/tlp-250-toshiba-99104964")
      )
      (libsource (lib "YAYAT-LIB") (part "TLP250"))
    )
    (comp (ref "TLPb2")
      (value "TLP250")
      (footprint "Opto-Coupler-TLP250")
      (description "Optocoupler Drive Push-Pull 1-CH 30V 600V 8-Pin PDIP")
      (fields
        (field (name "MANUFACTURER") "TOSHIBA")
        (field (name "OCTOPART") "https://octopart.com/tlp-250-toshiba-99104964")
      )
      (libsource (lib "YAYAT-LIB") (part "TLP250"))
    )
    (comp (ref "TLPc1")
      (value "TLP250")
      (footprint "Opto-Coupler-TLP250")
      (description "Optocoupler Drive Push-Pull 1-CH 30V 600V 8-Pin PDIP")
      (fields
        (field (name "MANUFACTURER") "TOSHIBA")
        (field (name "OCTOPART") "https://octopart.com/tlp-250-toshiba-99104964")
      )
      (libsource (lib "YAYAT-LIB") (part "TLP250"))
    )
    (comp (ref "TLPc2")
      (value "TLP250")
      (footprint "Opto-Coupler-TLP250")
      (description "Optocoupler Drive Push-Pull 1-CH 30V 600V 8-Pin PDIP")
      (fields
        (field (name "MANUFACTURER") "TOSHIBA")
        (field (name "OCTOPART") "https://octopart.com/tlp-250-toshiba-99104964")
      )
      (libsource (lib "YAYAT-LIB") (part "TLP250"))
    )
    (comp (ref "U1")
      (value "LM317T/NOPB")
      (footprint "Voltage-Regulator-LM317")
      (description "3-Terminal Adjustable Regulator, 3-pin TO-220, Pb-Free")
      (fields (field (name "MANUFACTURER") "Texas Instruments"))
      (libsource (lib "YAYAT-LIB") (part "Voltage-Regulator-LM317"))
    )
    (comp (ref "VR1")
      (value "3296W-1-103LF")
      (footprint "Resistor-Trimmer")
      (fields (field (name "TOLERANCE") "1%"))
      (libsource (lib "YAYAT-LIB") (part "Resistor-Trimmer"))
    )
  )
  (nets
    (net (code "1") (name "/G1") (class "Default")
      (node (ref "RG1") (pin "1") (pinfunction "1_1") (pintype "passive"))
    )
    (net (code "2") (name "/G2") (class "Default")
      (node (ref "RG2") (pin "1") (pinfunction "1_1") (pintype "passive"))
    )
    (net (code "3") (name "/G3") (class "Default")
      (node (ref "RG3") (pin "1") (pinfunction "1_1") (pintype "passive"))
    )
    (net (code "4") (name "/G4") (class "Default")
      (node (ref "RG4") (pin "1") (pinfunction "1_1") (pintype "passive"))
    )
    (net (code "5") (name "/G5") (class "Default")
      (node (ref "RG5") (pin "1") (pinfunction "1_1") (pintype "passive"))
    )
    (net (code "6") (name "/G6") (class "Default")
      (node (ref "RG6") (pin "1") (pinfunction "1_1") (pintype "passive"))
    )
    (net (code "7") (name "/P1") (class "Default")
      (node (ref "Ca4") (pin "2") (pinfunction "2_2") (pintype "passive"))
      (node (ref "Ca5") (pin "1") (pinfunction "1_1") (pintype "passive"))
      (node (ref "D1a") (pin "1") (pinfunction "A_1") (pintype "passive"))
      (node (ref "D1b") (pin "1") (pinfunction "A_1") (pintype "passive"))
      (node (ref "IRa") (pin "5") (pinfunction "VS_5") (pintype "power_in"))
      (node (ref "Q1a") (pin "3") (pinfunction "S_3") (pintype "passive"))
      (node (ref "Q1b") (pin "3") (pinfunction "S_3") (pintype "passive"))
      (node (ref "Q2a") (pin "2") (pinfunction "D_2") (pintype "passive"))
      (node (ref "Q2b") (pin "2") (pinfunction "D_2") (pintype "passive"))
      (node (ref "R1b") (pin "2") (pinfunction "2_2") (pintype "passive"))
      (node (ref "R1d") (pin "2") (pinfunction "2_2") (pintype "passive"))
    )
    (net (code "8") (name "/P2") (class "Default")
      (node (ref "Cb4") (pin "2") (pinfunction "2_2") (pintype "passive"))
      (node (ref "Cb5") (pin "1") (pinfunction "1_1") (pintype "passive"))
      (node (ref "D3a") (pin "1") (pinfunction "A_1") (pintype "passive"))
      (node (ref "D3b") (pin "1") (pinfunction "A_1") (pintype "passive"))
      (node (ref "IRb") (pin "5") (pinfunction "VS_5") (pintype "power_in"))
      (node (ref "Q3a") (pin "3") (pinfunction "S_3") (pintype "passive"))
      (node (ref "Q3b") (pin "3") (pinfunction "S_3") (pintype "passive"))
      (node (ref "Q4a") (pin "2") (pinfunction "D_2") (pintype "passive"))
      (node (ref "Q4b") (pin "2") (pinfunction "D_2") (pintype "passive"))
      (node (ref "R3b") (pin "1") (pinfunction "1_1") (pintype "passive"))
      (node (ref "R3d") (pin "1") (pinfunction "1_1") (pintype "passive"))
    )
    (net (code "9") (name "/P3") (class "Default")
      (node (ref "Cc4") (pin "2") (pinfunction "2_2") (pintype "passive"))
      (node (ref "Cc5") (pin "1") (pinfunction "1_1") (pintype "passive"))
      (node (ref "D5a") (pin "1") (pinfunction "A_1") (pintype "passive"))
      (node (ref "D5b") (pin "1") (pinfunction "A_1") (pintype "passive"))
      (node (ref "IRc") (pin "5") (pinfunction "VS_5") (pintype "power_in"))
      (node (ref "Q5a") (pin "3") (pinfunction "S_3") (pintype "passive"))
      (node (ref "Q5b") (pin "3") (pinfunction "S_3") (pintype "passive"))
      (node (ref "Q6a") (pin "2") (pinfunction "D_2") (pintype "passive"))
      (node (ref "Q6b") (pin "2") (pinfunction "D_2") (pintype "passive"))
      (node (ref "R5b") (pin "1") (pinfunction "1_1") (pintype "passive"))
      (node (ref "R5d") (pin "1") (pinfunction "1_1") (pintype "passive"))
    )
    (net (code "10") (name "15V") (class "Default")
      (node (ref "C3") (pin "2") (pinfunction "2_2") (pintype "passive"))
      (node (ref "Ca1") (pin "2") (pinfunction "2_2") (pintype "passive"))
      (node (ref "Ca2") (pin "2") (pinfunction "2_2") (pintype "passive"))
      (node (ref "Ca3") (pin "1") (pinfunction "1_1") (pintype "passive"))
      (node (ref "Cb1") (pin "2") (pinfunction "2_2") (pintype "passive"))
      (node (ref "Cb2") (pin "2") (pinfunction "2_2") (pintype "passive"))
      (node (ref "Cb3") (pin "1") (pinfunction "1_1") (pintype "passive"))
      (node (ref "Cc1") (pin "2") (pinfunction "2_2") (pintype "passive"))
      (node (ref "Cc2") (pin "2") (pinfunction "2_2") (pintype "passive"))
      (node (ref "Cc3") (pin "1") (pinfunction "1_1") (pintype "passive"))
      (node (ref "D1") (pin "1") (pinfunction "A_1") (pintype "passive"))
      (node (ref "D2") (pin "2") (pinfunction "K_2") (pintype "passive"))
      (node (ref "Da") (pin "2") (pinfunction "A_2") (pintype "passive"))
      (node (ref "Db") (pin "2") (pinfunction "A_2") (pintype "passive"))
      (node (ref "Dc") (pin "2") (pinfunction "A_2") (pintype "passive"))
      (node (ref "IRa") (pin "3") (pinfunction "VCC_3") (pintype "power_in"))
      (node (ref "IRa") (pin "9") (pinfunction "VDD_9") (pintype "power_in"))
      (node (ref "IRb") (pin "3") (pinfunction "VCC_3") (pintype "power_in"))
      (node (ref "IRb") (pin "9") (pinfunction "VDD_9") (pintype "power_in"))
      (node (ref "IRc") (pin "3") (pinfunction "VCC_3") (pintype "power_in"))
      (node (ref "IRc") (pin "9") (pinfunction "VDD_9") (pintype "power_in"))
      (node (ref "J1") (pin "1") (pinfunction "1_1") (pintype "passive"))
      (node (ref "R1") (pin "2") (pinfunction "2_2") (pintype "passive"))
      (node (ref "TLPa1") (pin "8") (pinfunction "VCC_8") (pintype "power_in"))
      (node (ref "TLPa2") (pin "8") (pinfunction "VCC_8") (pintype "power_in"))
      (node (ref "TLPb1") (pin "8") (pinfunction "VCC_8") (pintype "power_in"))
      (node (ref "TLPb2") (pin "8") (pinfunction "VCC_8") (pintype "power_in"))
      (node (ref "TLPc1") (pin "8") (pinfunction "VCC_8") (pintype "power_in"))
      (node (ref "TLPc2") (pin "8") (pinfunction "VCC_8") (pintype "power_in"))
      (node (ref "U1") (pin "2") (pinfunction "OUT_2") (pintype "power_in"))
    )
    (net (code "11") (name "36V_I") (class "Default")
      (node (ref "C4") (pin "1") (pinfunction "1_1") (pintype "passive"))
      (node (ref "C5") (pin "1") (pinfunction "1_1") (pintype "passive"))
      (node (ref "C6") (pin "1") (pinfunction "1_1") (pintype "passive"))
      (node (ref "D3") (pin "2") (pinfunction "K_2") (pintype "passive"))
      (node (ref "Q1a") (pin "2") (pinfunction "D_2") (pintype "passive"))
      (node (ref "Q1b") (pin "2") (pinfunction "D_2") (pintype "passive"))
      (node (ref "Q3a") (pin "2") (pinfunction "D_2") (pintype "passive"))
      (node (ref "Q3b") (pin "2") (pinfunction "D_2") (pintype "passive"))
      (node (ref "Q5a") (pin "2") (pinfunction "D_2") (pintype "passive"))
      (node (ref "Q5b") (pin "2") (pinfunction "D_2") (pintype "passive"))
    )
    (net (code "12") (name "36V_P") (class "Default")
      (node (ref "C1") (pin "2") (pinfunction "2_2") (pintype "passive"))
      (node (ref "C15") (pin "1") (pinfunction "1_1") (pintype "passive"))
      (node (ref "D1") (pin "2") (pinfunction "K_2") (pintype "passive"))
      (node (ref "D4") (pin "2") (pinfunction "K_2") (pintype "passive"))
      (node (ref "U1") (pin "3") (pinfunction "IN_3") (pintype "power_in"))
    )
    (net (code "13") (name "FGND2") (class "Default")
      (node (ref "TLPa1") (pin "3") (pinfunction "C_3") (pintype "passive"))
      (node (ref "TLPa2") (pin "3") (pinfunction "C_3") (pintype "passive"))
      (node (ref "TLPb1") (pin "3") (pinfunction "C_3") (pintype "passive"))
      (node (ref "TLPb2") (pin "3") (pinfunction "C_3") (pintype "passive"))
      (node (ref "TLPc1") (pin "3") (pinfunction "C_3") (pintype "passive"))
      (node (ref "TLPc2") (pin "3") (pinfunction "C_3") (pintype "passive"))
    )
    (net (code "14") (name "GND") (class "Default")
      (node (ref "C1") (pin "1") (pinfunction "1_1") (pintype "passive"))
      (node (ref "C15") (pin "2") (pinfunction "2_2") (pintype "passive"))
      (node (ref "C2") (pin "1") (pinfunction "1_1") (pintype "passive"))
      (node (ref "C3") (pin "1") (pinfunction "1_1") (pintype "passive"))
      (node (ref "C4") (pin "2") (pinfunction "2_2") (pintype "passive"))
      (node (ref "C5") (pin "2") (pinfunction "2_2") (pintype "passive"))
      (node (ref "C6") (pin "2") (pinfunction "2_2") (pintype "passive"))
      (node (ref "Ca1") (pin "1") (pinfunction "1_1") (pintype "passive"))
      (node (ref "Ca2") (pin "1") (pinfunction "1_1") (pintype "passive"))
      (node (ref "Ca3") (pin "2") (pinfunction "2_2") (pintype "passive"))
      (node (ref "Cb1") (pin "1") (pinfunction "1_1") (pintype "passive"))
      (node (ref "Cb2") (pin "1") (pinfunction "1_1") (pintype "passive"))
      (node (ref "Cb3") (pin "2") (pinfunction "2_2") (pintype "passive"))
      (node (ref "Cc1") (pin "1") (pinfunction "1_1") (pintype "passive"))
      (node (ref "Cc2") (pin "1") (pinfunction "1_1") (pintype "passive"))
      (node (ref "Cc3") (pin "2") (pinfunction "2_2") (pintype "passive"))
      (node (ref "D2a") (pin "1") (pinfunction "A_1") (pintype "passive"))
      (node (ref "D2b") (pin "1") (pinfunction "A_1") (pintype "passive"))
      (node (ref "D4a") (pin "1") (pinfunction "A_1") (pintype "passive"))
      (node (ref "D4b") (pin "1") (pinfunction "A_1") (pintype "passive"))
      (node (ref "D6a") (pin "1") (pinfunction "A_1") (pintype "passive"))
      (node (ref "D6b") (pin "1") (pinfunction "A_1") (pintype "passive"))
      (node (ref "IRa") (pin "11") (pinfunction "SD_11") (pintype "input"))
      (node (ref "IRa") (pin "13") (pinfunction "VSS_13") (pintype "power_in"))
      (node (ref "IRa") (pin "2") (pinfunction "COM_2") (pintype "passive"))
      (node (ref "IRb") (pin "11") (pinfunction "SD_11") (pintype "input"))
      (node (ref "IRb") (pin "13") (pinfunction "VSS_13") (pintype "power_in"))
      (node (ref "IRb") (pin "2") (pinfunction "COM_2") (pintype "passive"))
      (node (ref "IRc") (pin "11") (pinfunction "SD_11") (pintype "input"))
      (node (ref "IRc") (pin "13") (pinfunction "VSS_13") (pintype "power_in"))
      (node (ref "IRc") (pin "2") (pinfunction "COM_2") (pintype "passive"))
      (node (ref "J2") (pin "1") (pinfunction "1_1") (pintype "passive"))
      (node (ref "Q2a") (pin "3") (pinfunction "S_3") (pintype "passive"))
      (node (ref "Q2b") (pin "3") (pinfunction "S_3") (pintype "passive"))
      (node (ref "Q4a") (pin "3") (pinfunction "S_3") (pintype "passive"))
      (node (ref "Q4b") (pin "3") (pinfunction "S_3") (pintype "passive"))
      (node (ref "Q6a") (pin "3") (pinfunction "S_3") (pintype "passive"))
      (node (ref "Q6b") (pin "3") (pinfunction "S_3") (pintype "passive"))
      (node (ref "R2b") (pin "2") (pinfunction "2_2") (pintype "passive"))
      (node (ref "R2d") (pin "2") (pinfunction "2_2") (pintype "passive"))
      (node (ref "R4b") (pin "1") (pinfunction "1_1") (pintype "passive"))
      (node (ref "R4d") (pin "1") (pinfunction "1_1") (pintype "passive"))
      (node (ref "R6b") (pin "1") (pinfunction "1_1") (pintype "passive"))
      (node (ref "R6d") (pin "1") (pinfunction "1_1") (pintype "passive"))
      (node (ref "TLPa1") (pin "5") (pinfunction "GND_5") (pintype "power_in"))
      (node (ref "TLPa2") (pin "5") (pinfunction "GND_5") (pintype "power_in"))
      (node (ref "TLPb1") (pin "5") (pinfunction "GND_5") (pintype "power_in"))
      (node (ref "TLPb2") (pin "5") (pinfunction "GND_5") (pintype "power_in"))
      (node (ref "TLPc1") (pin "5") (pinfunction "GND_5") (pintype "power_in"))
      (node (ref "TLPc2") (pin "5") (pinfunction "GND_5") (pintype "power_in"))
      (node (ref "VR1") (pin "2") (pinfunction "S_2") (pintype "passive"))
      (node (ref "VR1") (pin "3") (pinfunction "CW_3") (pintype "passive"))
    )
    (net (code "15") (name "Net-(D1a-K)") (class "Default")
      (node (ref "D1a") (pin "2") (pinfunction "K_2") (pintype "passive"))
      (node (ref "Q1a") (pin "1") (pinfunction "G_1") (pintype "passive"))
      (node (ref "R1a") (pin "2") (pinfunction "2_2") (pintype "passive"))
      (node (ref "R1b") (pin "1") (pinfunction "1_1") (pintype "passive"))
    )
    (net (code "16") (name "Net-(D1b-K)") (class "Default")
      (node (ref "D1b") (pin "2") (pinfunction "K_2") (pintype "passive"))
      (node (ref "Q1b") (pin "1") (pinfunction "G_1") (pintype "passive"))
      (node (ref "R1c") (pin "2") (pinfunction "2_2") (pintype "passive"))
      (node (ref "R1d") (pin "1") (pinfunction "1_1") (pintype "passive"))
    )
    (net (code "17") (name "Net-(D2-A)") (class "Default")
      (node (ref "C2") (pin "2") (pinfunction "2_2") (pintype "passive"))
      (node (ref "D2") (pin "1") (pinfunction "A_1") (pintype "passive"))
      (node (ref "R1") (pin "1") (pinfunction "1_1") (pintype "passive"))
      (node (ref "U1") (pin "1") (pinfunction "ADJ_1") (pintype "input"))
      (node (ref "VR1") (pin "1") (pinfunction "CCW_1") (pintype "passive"))
    )
    (net (code "18") (name "Net-(D2a-K)") (class "Default")
      (node (ref "D2a") (pin "2") (pinfunction "K_2") (pintype "passive"))
      (node (ref "Q2a") (pin "1") (pinfunction "G_1") (pintype "passive"))
      (node (ref "R2a") (pin "2") (pinfunction "2_2") (pintype "passive"))
      (node (ref "R2b") (pin "1") (pinfunction "1_1") (pintype "passive"))
    )
    (net (code "19") (name "Net-(D2b-K)") (class "Default")
      (node (ref "D2b") (pin "2") (pinfunction "K_2") (pintype "passive"))
      (node (ref "Q2b") (pin "1") (pinfunction "G_1") (pintype "passive"))
      (node (ref "R2c") (pin "2") (pinfunction "2_2") (pintype "passive"))
      (node (ref "R2d") (pin "1") (pinfunction "1_1") (pintype "passive"))
    )
    (net (code "20") (name "Net-(D3a-K)") (class "Default")
      (node (ref "D3a") (pin "2") (pinfunction "K_2") (pintype "passive"))
      (node (ref "Q3a") (pin "1") (pinfunction "G_1") (pintype "passive"))
      (node (ref "R3a") (pin "2") (pinfunction "2_2") (pintype "passive"))
      (node (ref "R3b") (pin "2") (pinfunction "2_2") (pintype "passive"))
    )
    (net (code "21") (name "Net-(D3b-K)") (class "Default")
      (node (ref "D3b") (pin "2") (pinfunction "K_2") (pintype "passive"))
      (node (ref "Q3b") (pin "1") (pinfunction "G_1") (pintype "passive"))
      (node (ref "R3c") (pin "2") (pinfunction "2_2") (pintype "passive"))
      (node (ref "R3d") (pin "2") (pinfunction "2_2") (pintype "passive"))
    )
    (net (code "22") (name "Net-(D4a-K)") (class "Default")
      (node (ref "D4a") (pin "2") (pinfunction "K_2") (pintype "passive"))
      (node (ref "Q4a") (pin "1") (pinfunction "G_1") (pintype "passive"))
      (node (ref "R4a") (pin "2") (pinfunction "2_2") (pintype "passive"))
      (node (ref "R4b") (pin "2") (pinfunction "2_2") (pintype "passive"))
    )
    (net (code "23") (name "Net-(D4b-K)") (class "Default")
      (node (ref "D4b") (pin "2") (pinfunction "K_2") (pintype "passive"))
      (node (ref "Q4b") (pin "1") (pinfunction "G_1") (pintype "passive"))
      (node (ref "R4c") (pin "2") (pinfunction "2_2") (pintype "passive"))
      (node (ref "R4d") (pin "2") (pinfunction "2_2") (pintype "passive"))
    )
    (net (code "24") (name "Net-(D5a-K)") (class "Default")
      (node (ref "D5a") (pin "2") (pinfunction "K_2") (pintype "passive"))
      (node (ref "Q5a") (pin "1") (pinfunction "G_1") (pintype "passive"))
      (node (ref "R5a") (pin "2") (pinfunction "2_2") (pintype "passive"))
      (node (ref "R5b") (pin "2") (pinfunction "2_2") (pintype "passive"))
    )
    (net (code "25") (name "Net-(D5b-K)") (class "Default")
      (node (ref "D5b") (pin "2") (pinfunction "K_2") (pintype "passive"))
      (node (ref "Q5b") (pin "1") (pinfunction "G_1") (pintype "passive"))
      (node (ref "R5c") (pin "2") (pinfunction "2_2") (pintype "passive"))
      (node (ref "R5d") (pin "2") (pinfunction "2_2") (pintype "passive"))
    )
    (net (code "26") (name "Net-(D6a-K)") (class "Default")
      (node (ref "D6a") (pin "2") (pinfunction "K_2") (pintype "passive"))
      (node (ref "Q6a") (pin "1") (pinfunction "G_1") (pintype "passive"))
      (node (ref "R6a") (pin "2") (pinfunction "2_2") (pintype "passive"))
      (node (ref "R6b") (pin "2") (pinfunction "2_2") (pintype "passive"))
    )
    (net (code "27") (name "Net-(D6b-K)") (class "Default")
      (node (ref "D6b") (pin "2") (pinfunction "K_2") (pintype "passive"))
      (node (ref "Q6b") (pin "1") (pinfunction "G_1") (pintype "passive"))
      (node (ref "R6c") (pin "2") (pinfunction "2_2") (pintype "passive"))
      (node (ref "R6d") (pin "2") (pinfunction "2_2") (pintype "passive"))
    )
    (net (code "28") (name "Net-(Da-C)") (class "Default")
      (node (ref "Ca4") (pin "1") (pinfunction "1_1") (pintype "passive"))
      (node (ref "Ca5") (pin "2") (pinfunction "2_2") (pintype "passive"))
      (node (ref "Da") (pin "1") (pinfunction "C_1") (pintype "passive"))
      (node (ref "IRa") (pin "6") (pinfunction "VB_6") (pintype "power_in"))
    )
    (net (code "29") (name "Net-(Db-C)") (class "Default")
      (node (ref "Cb4") (pin "1") (pinfunction "1_1") (pintype "passive"))
      (node (ref "Cb5") (pin "2") (pinfunction "2_2") (pintype "passive"))
      (node (ref "Db") (pin "1") (pinfunction "C_1") (pintype "passive"))
      (node (ref "IRb") (pin "6") (pinfunction "VB_6") (pintype "power_in"))
    )
    (net (code "30") (name "Net-(Dc-C)") (class "Default")
      (node (ref "Cc4") (pin "1") (pinfunction "1_1") (pintype "passive"))
      (node (ref "Cc5") (pin "2") (pinfunction "2_2") (pintype "passive"))
      (node (ref "Dc") (pin "1") (pinfunction "C_1") (pintype "passive"))
      (node (ref "IRc") (pin "6") (pinfunction "VB_6") (pintype "power_in"))
    )
    (net (code "31") (name "Net-(IRa-HIN)") (class "Default")
      (node (ref "IRa") (pin "10") (pinfunction "HIN_10") (pintype "input"))
      (node (ref "TLPa1") (pin "6") (pinfunction "VO(Output)_6") (pintype "output"))
    )
    (net (code "32") (name "Net-(IRa-HO)") (class "Default")
      (node (ref "IRa") (pin "7") (pinfunction "HO_7") (pintype "output"))
      (node (ref "R1a") (pin "1") (pinfunction "1_1") (pintype "passive"))
      (node (ref "R1c") (pin "1") (pinfunction "1_1") (pintype "passive"))
    )
    (net (code "33") (name "Net-(IRa-LIN)") (class "Default")
      (node (ref "IRa") (pin "12") (pinfunction "LIN_12") (pintype "input"))
      (node (ref "TLPa2") (pin "6") (pinfunction "VO(Output)_6") (pintype "output"))
    )
    (net (code "34") (name "Net-(IRa-LO)") (class "Default")
      (node (ref "IRa") (pin "1") (pinfunction "LO_1") (pintype "output"))
      (node (ref "R2a") (pin "1") (pinfunction "1_1") (pintype "passive"))
      (node (ref "R2c") (pin "1") (pinfunction "1_1") (pintype "passive"))
    )
    (net (code "35") (name "Net-(IRb-HIN)") (class "Default")
      (node (ref "IRb") (pin "10") (pinfunction "HIN_10") (pintype "input"))
      (node (ref "TLPb1") (pin "6") (pinfunction "VO(Output)_6") (pintype "output"))
    )
    (net (code "36") (name "Net-(IRb-HO)") (class "Default")
      (node (ref "IRb") (pin "7") (pinfunction "HO_7") (pintype "output"))
      (node (ref "R3a") (pin "1") (pinfunction "1_1") (pintype "passive"))
      (node (ref "R3c") (pin "1") (pinfunction "1_1") (pintype "passive"))
    )
    (net (code "37") (name "Net-(IRb-LIN)") (class "Default")
      (node (ref "IRb") (pin "12") (pinfunction "LIN_12") (pintype "input"))
      (node (ref "TLPb2") (pin "6") (pinfunction "VO(Output)_6") (pintype "output"))
    )
    (net (code "38") (name "Net-(IRb-LO)") (class "Default")
      (node (ref "IRb") (pin "1") (pinfunction "LO_1") (pintype "output"))
      (node (ref "R4a") (pin "1") (pinfunction "1_1") (pintype "passive"))
      (node (ref "R4c") (pin "1") (pinfunction "1_1") (pintype "passive"))
    )
    (net (code "39") (name "Net-(IRc-HIN)") (class "Default")
      (node (ref "IRc") (pin "10") (pinfunction "HIN_10") (pintype "input"))
      (node (ref "TLPc1") (pin "6") (pinfunction "VO(Output)_6") (pintype "output"))
    )
    (net (code "40") (name "Net-(IRc-HO)") (class "Default")
      (node (ref "IRc") (pin "7") (pinfunction "HO_7") (pintype "output"))
      (node (ref "R5a") (pin "1") (pinfunction "1_1") (pintype "passive"))
      (node (ref "R5c") (pin "1") (pinfunction "1_1") (pintype "passive"))
    )
    (net (code "41") (name "Net-(IRc-LIN)") (class "Default")
      (node (ref "IRc") (pin "12") (pinfunction "LIN_12") (pintype "input"))
      (node (ref "TLPc2") (pin "6") (pinfunction "VO(Output)_6") (pintype "output"))
    )
    (net (code "42") (name "Net-(IRc-LO)") (class "Default")
      (node (ref "IRc") (pin "1") (pinfunction "LO_1") (pintype "output"))
      (node (ref "R6a") (pin "1") (pinfunction "1_1") (pintype "passive"))
      (node (ref "R6c") (pin "1") (pinfunction "1_1") (pintype "passive"))
    )
    (net (code "43") (name "Net-(TLPa1-A)") (class "Default")
      (node (ref "RG1") (pin "2") (pinfunction "2_2") (pintype "passive"))
      (node (ref "TLPa1") (pin "2") (pinfunction "A_2") (pintype "passive"))
    )
    (net (code "44") (name "Net-(TLPa2-A)") (class "Default")
      (node (ref "RG2") (pin "2") (pinfunction "2_2") (pintype "passive"))
      (node (ref "TLPa2") (pin "2") (pinfunction "A_2") (pintype "passive"))
    )
    (net (code "45") (name "Net-(TLPb1-A)") (class "Default")
      (node (ref "RG3") (pin "2") (pinfunction "2_2") (pintype "passive"))
      (node (ref "TLPb1") (pin "2") (pinfunction "A_2") (pintype "passive"))
    )
    (net (code "46") (name "Net-(TLPb2-A)") (class "Default")
      (node (ref "RG4") (pin "2") (pinfunction "2_2") (pintype "passive"))
      (node (ref "TLPb2") (pin "2") (pinfunction "A_2") (pintype "passive"))
    )
    (net (code "47") (name "Net-(TLPc1-A)") (class "Default")
      (node (ref "RG5") (pin "2") (pinfunction "2_2") (pintype "passive"))
      (node (ref "TLPc1") (pin "2") (pinfunction "A_2") (pintype "passive"))
    )
    (net (code "48") (name "Net-(TLPc2-A)") (class "Default")
      (node (ref "RG6") (pin "2") (pinfunction "2_2") (pintype "passive"))
      (node (ref "TLPc2") (pin "2") (pinfunction "A_2") (pintype "passive"))
    )
    (net (code "49") (name "VCC") (class "Default")
      (node (ref "D3") (pin "1") (pinfunction "A_1") (pintype "passive"))
      (node (ref "D4") (pin "1") (pinfunction "A_1") (pintype "passive"))
    )
    (net (code "50") (name "unconnected-(IRa-NC-Pad4)") (class "Default")
      (node (ref "IRa") (pin "4") (pinfunction "NC_4") (pintype "input+no_connect"))
    )
    (net (code "51") (name "unconnected-(IRa-NC_2-Pad8)") (class "Default")
      (node (ref "IRa") (pin "8") (pinfunction "NC_2_8") (pintype "input+no_connect"))
    )
    (net (code "52") (name "unconnected-(IRa-NC_3-Pad14)") (class "Default")
      (node (ref "IRa") (pin "14") (pinfunction "NC_3_14") (pintype "input+no_connect"))
    )
    (net (code "53") (name "unconnected-(IRb-NC-Pad4)") (class "Default")
      (node (ref "IRb") (pin "4") (pinfunction "NC_4") (pintype "input+no_connect"))
    )
    (net (code "54") (name "unconnected-(IRb-NC_2-Pad8)") (class "Default")
      (node (ref "IRb") (pin "8") (pinfunction "NC_2_8") (pintype "input+no_connect"))
    )
    (net (code "55") (name "unconnected-(IRb-NC_3-Pad14)") (class "Default")
      (node (ref "IRb") (pin "14") (pinfunction "NC_3_14") (pintype "input+no_connect"))
    )
    (net (code "56") (name "unconnected-(IRc-NC-Pad4)") (class "Default")
      (node (ref "IRc") (pin "4") (pinfunction "NC_4") (pintype "input+no_connect"))
    )
    (net (code "57") (name "unconnected-(IRc-NC_2-Pad8)") (class "Default")
      (node (ref "IRc") (pin "8") (pinfunction "NC_2_8") (pintype "input+no_connect"))
    )
    (net (code "58") (name "unconnected-(IRc-NC_3-Pad14)") (class "Default")
      (node (ref "IRc") (pin "14") (pinfunction "NC_3_14") (pintype "input+no_connect"))
    )
    (net (code "59") (name "unconnected-(TLPa1-NC-Pad1)") (class "Default")
      (node (ref "TLPa1") (pin "1") (pinfunction "NC_1") (pintype "passive+no_connect"))
    )
    (net (code "60") (name "unconnected-(TLPa1-NC-Pad4)") (class "Default")
      (node (ref "TLPa1") (pin "4") (pinfunction "NC_4") (pintype "passive+no_connect"))
    )
    (net (code "61") (name "unconnected-(TLPa1-VO-Pad7)") (class "Default")
      (node (ref "TLPa1") (pin "7") (pinfunction "VO_7") (pintype "output+no_connect"))
    )
    (net (code "62") (name "unconnected-(TLPa2-NC-Pad1)") (class "Default")
      (node (ref "TLPa2") (pin "1") (pinfunction "NC_1") (pintype "passive+no_connect"))
    )
    (net (code "63") (name "unconnected-(TLPa2-NC-Pad4)") (class "Default")
      (node (ref "TLPa2") (pin "4") (pinfunction "NC_4") (pintype "passive+no_connect"))
    )
    (net (code "64") (name "unconnected-(TLPa2-VO-Pad7)") (class "Default")
      (node (ref "TLPa2") (pin "7") (pinfunction "VO_7") (pintype "output+no_connect"))
    )
    (net (code "65") (name "unconnected-(TLPb1-NC-Pad1)") (class "Default")
      (node (ref "TLPb1") (pin "1") (pinfunction "NC_1") (pintype "passive+no_connect"))
    )
    (net (code "66") (name "unconnected-(TLPb1-NC-Pad4)") (class "Default")
      (node (ref "TLPb1") (pin "4") (pinfunction "NC_4") (pintype "passive+no_connect"))
    )
    (net (code "67") (name "unconnected-(TLPb1-VO-Pad7)") (class "Default")
      (node (ref "TLPb1") (pin "7") (pinfunction "VO_7") (pintype "output+no_connect"))
    )
    (net (code "68") (name "unconnected-(TLPb2-NC-Pad1)") (class "Default")
      (node (ref "TLPb2") (pin "1") (pinfunction "NC_1") (pintype "passive+no_connect"))
    )
    (net (code "69") (name "unconnected-(TLPb2-NC-Pad4)") (class "Default")
      (node (ref "TLPb2") (pin "4") (pinfunction "NC_4") (pintype "passive+no_connect"))
    )
    (net (code "70") (name "unconnected-(TLPb2-VO-Pad7)") (class "Default")
      (node (ref "TLPb2") (pin "7") (pinfunction "VO_7") (pintype "output+no_connect"))
    )
    (net (code "71") (name "unconnected-(TLPc1-NC-Pad1)") (class "Default")
      (node (ref "TLPc1") (pin "1") (pinfunction "NC_1") (pintype "passive+no_connect"))
    )
    (net (code "72") (name "unconnected-(TLPc1-NC-Pad4)") (class "Default")
      (node (ref "TLPc1") (pin "4") (pinfunction "NC_4") (pintype "passive+no_connect"))
    )
    (net (code "73") (name "unconnected-(TLPc1-VO-Pad7)") (class "Default")
      (node (ref "TLPc1") (pin "7") (pinfunction "VO_7") (pintype "output+no_connect"))
    )
    (net (code "74") (name "unconnected-(TLPc2-NC-Pad1)") (class "Default")
      (node (ref "TLPc2") (pin "1") (pinfunction "NC_1") (pintype "passive+no_connect"))
    )
    (net (code "75") (name "unconnected-(TLPc2-NC-Pad4)") (class "Default")
      (node (ref "TLPc2") (pin "4") (pinfunction "NC_4") (pintype "passive+no_connect"))
    )
    (net (code "76") (name "unconnected-(TLPc2-VO-Pad7)") (class "Default")
      (node (ref "TLPc2") (pin "7") (pinfunction "VO_7") (pintype "output+no_connect"))
    )
  )
)
